# inktimev6.net
KiCad netlist of a schematic drawn in EAGLE
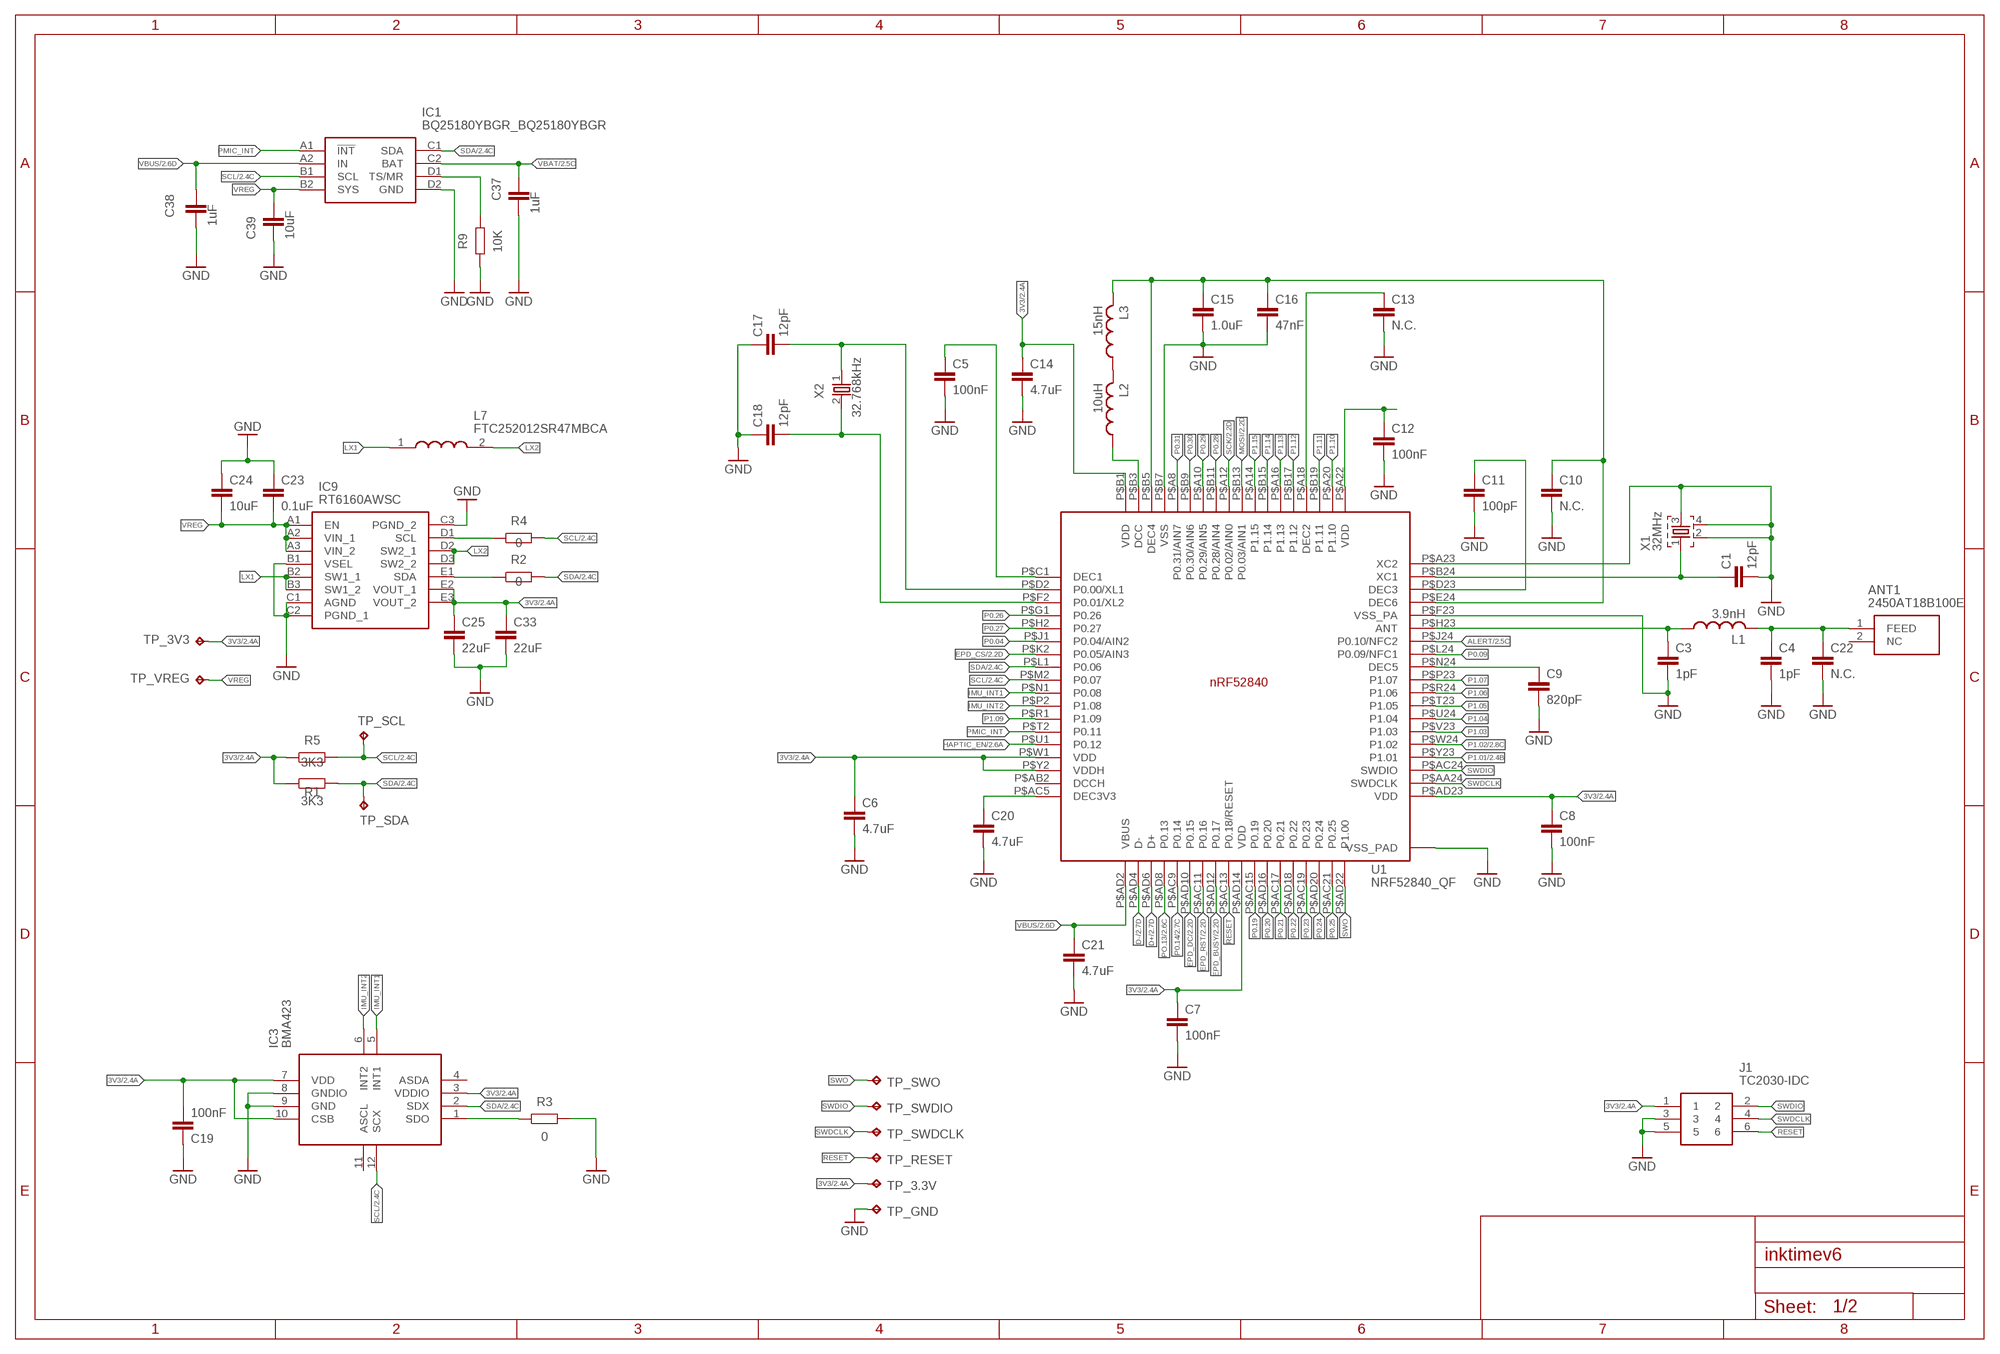
[diagram p0: schematic, sheet 1]
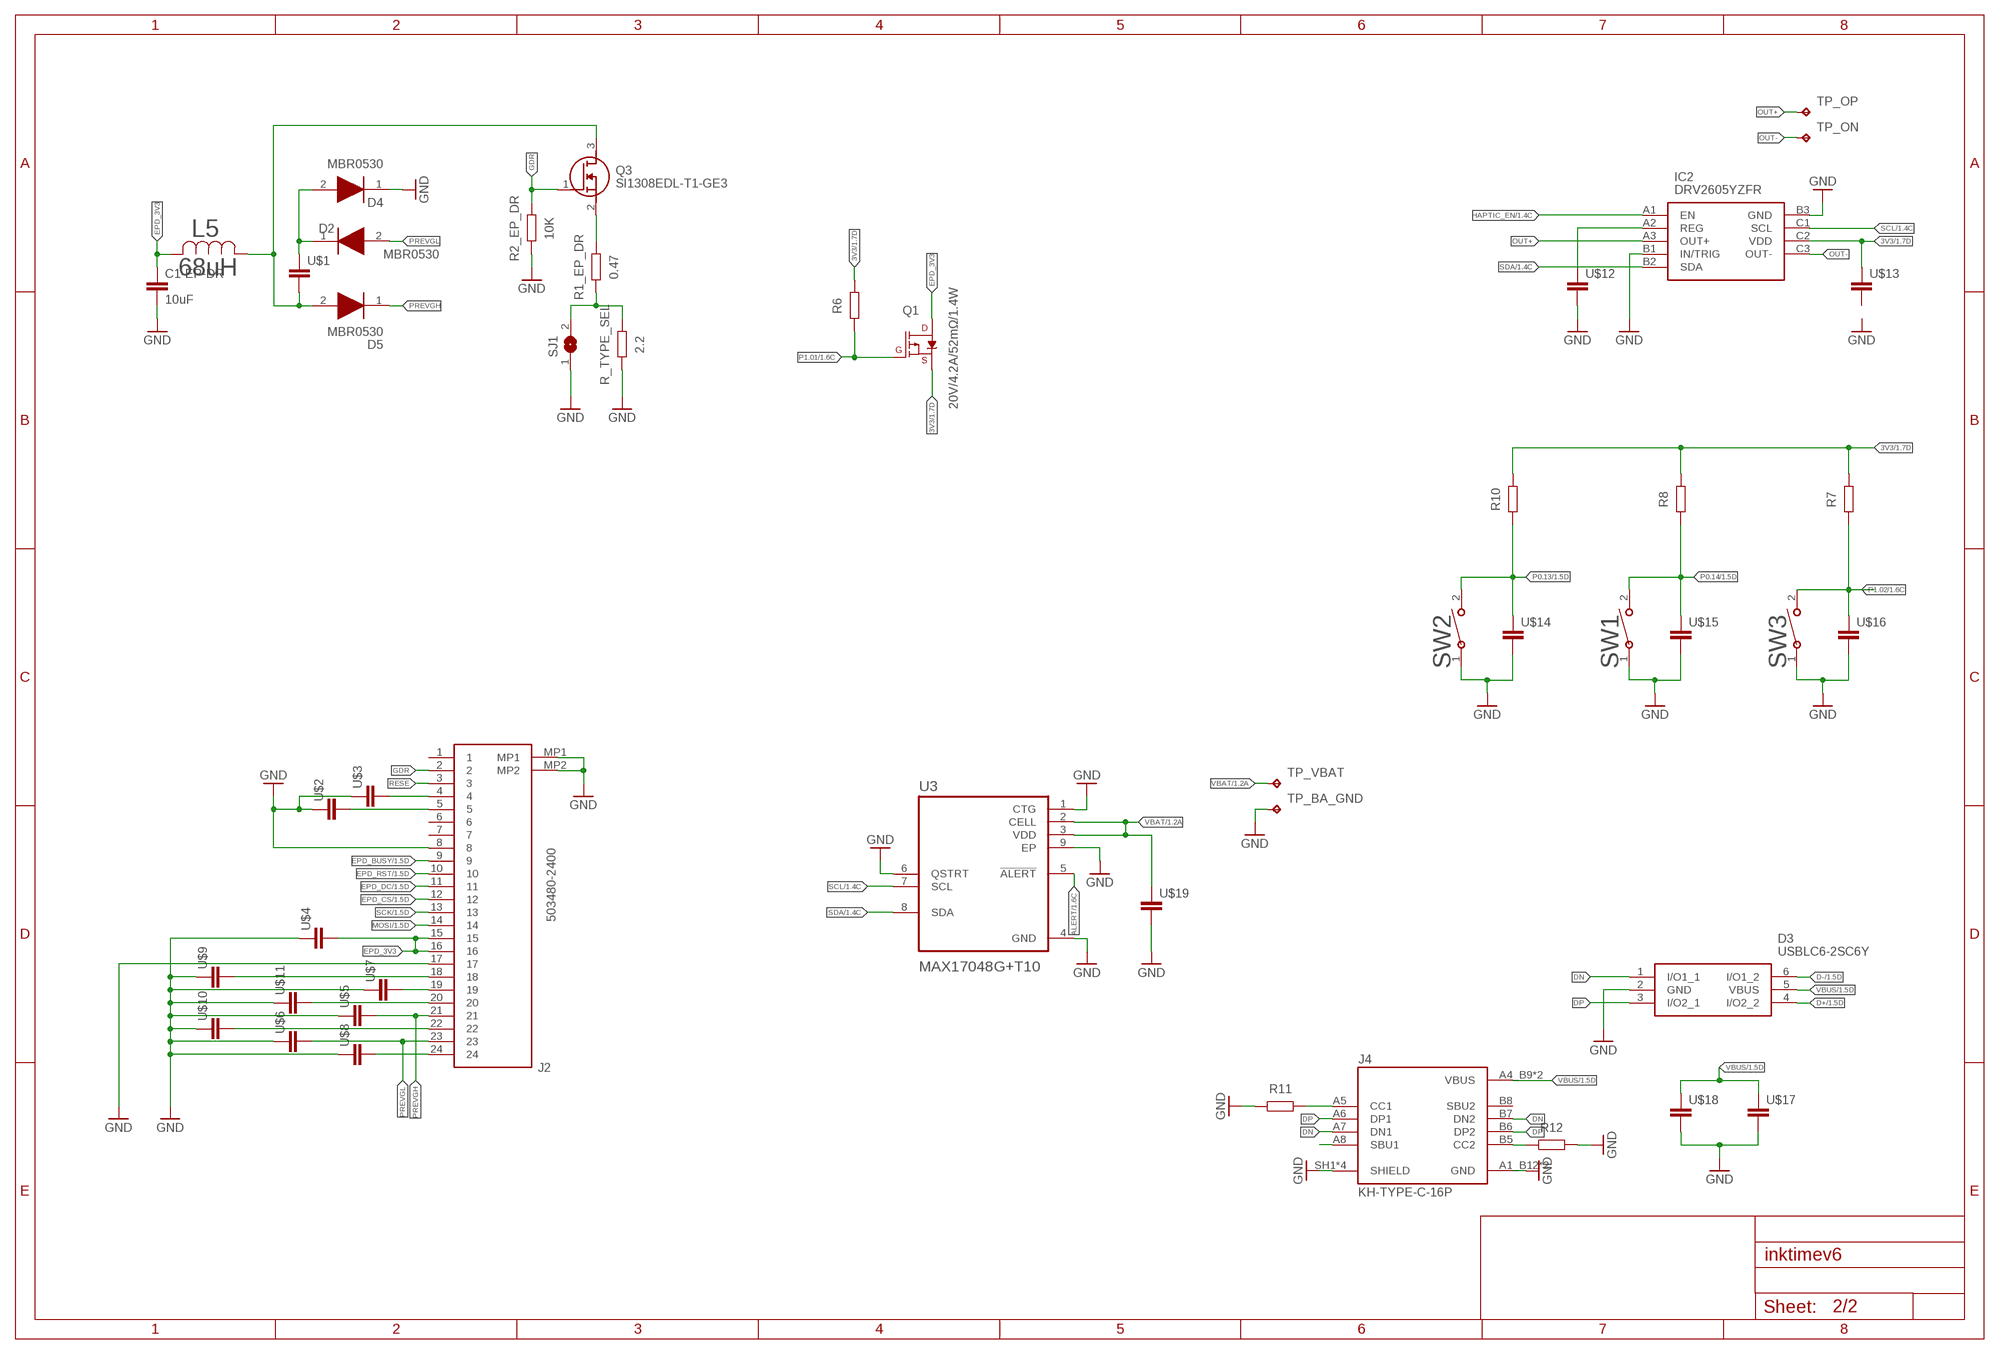
[diagram p1: schematic, sheet 2]

(export (version "E")
  (design (tool "Eeschema 10.0.6"))
  (components
    (comp (ref "C1-EP-DR")
      (value "10uF")
      (footprint "eagle-import:NORDIC_NRF_3_RESC0201_L")
      (libsource (lib "eagle-import") (part "NORDIC_NRF_3_CAPACITOR_0201_L"))
    )
    (comp (ref "D2")
      (value "MBR0530")
      (footprint "eagle-import:ESP32_C6_LIBRARY_5_SOD3716X135N")
      (fields (field (name "MF") "ON Semiconductor"))
      (libsource (lib "eagle-import") (part "ESP32_C6_LIBRARY_5_MBR0530"))
    )
    (comp (ref "D3")
      (value "USBLC6-2SC6Y")
      (footprint "eagle-import:ESP32_C6_LIBRARY_3_SOT95P280X145-6N")
      (fields (field (name "MF") "STMicroelectronics"))
      (libsource (lib "eagle-import") (part "ESP32_C6_LIBRARY_3_USBLC6-2SC6Y"))
    )
    (comp (ref "D4")
      (value "MBR0530")
      (footprint "eagle-import:ESP32_C6_LIBRARY_5_SOD3716X135N")
      (fields (field (name "MF") "ON Semiconductor"))
      (libsource (lib "eagle-import") (part "ESP32_C6_LIBRARY_5_MBR0530"))
    )
    (comp (ref "D5")
      (value "MBR0530")
      (footprint "eagle-import:ESP32_C6_LIBRARY_5_SOD3716X135N")
      (fields (field (name "MF") "ON Semiconductor"))
      (libsource (lib "eagle-import") (part "ESP32_C6_LIBRARY_5_MBR0530"))
    )
    (comp (ref "IC2")
      (value "DRV2605YZFR")
      (footprint "eagle-import:DRV2605YZFR_BGA9C50P3X3_144X144X62")
      (libsource (lib "eagle-import") (part "DRV2605YZFR_DRV2605YZFR"))
    )
    (comp (ref "J2")
      (value "503480-2400")
      (footprint "eagle-import:503480-2400_5034802400")
      (fields (field (name "MOUSER_PART_NUMBER") "538-503480-2400"))
      (libsource (lib "eagle-import") (part "503480-2400_503480-2400"))
    )
    (comp (ref "J4")
      (value "KH-TYPE-C-16P")
      (footprint "eagle-import:KH-TYPE-C-16P_KINGHELM_KH-TYPE-C-16P")
      (fields (field (name "MF") "kinghelm"))
      (libsource (lib "eagle-import") (part "KH-TYPE-C-16P_KH-TYPE-C-16P"))
    )
    (comp (ref "L5")
      (value "68uH")
      (footprint "eagle-import:ESP32_C6_LIBRARY_2_IND_4828-WE-TPC_WRE")
      (fields
        (field (name "MANUFACTURER_PART_NUMBER") "744043680")
        (field (name "COPYRIGHT") "Copyright (C) 2024 Ultra Librarian. All rights reserved.")
      )
      (libsource (lib "eagle-import") (part "ESP32_C6_LIBRARY_2_744043680IND_4828-WE-TPC_WRE"))
    )
    (comp (ref "Q1")
      (value "20V/4.2A/52mΩ/1.4W")
      (footprint "eagle-import:ESP32_C6_LIBRARY_4_ESP32_C6_LIBRARY_4_ESP32_C6_LIBRARY_4_ESP32_C6_LIBRARY_4_ESP32_WROVER_SPARKFUN-DISCRETESEMI_SOT23-3")
      (libsource (lib "eagle-import") (part "ESP32_C6_LIBRARY_4_ESP32_WROVER_SPARKFUN-DISCRETESEMI_MOSFET_PCH-DMG2305UX-7"))
    )
    (comp (ref "Q3")
      (value "SI1308EDL-T1-GE3")
      (footprint "eagle-import:ESP32_C6_LIBRARY_6_SOT65P210X110-3N")
      (fields (field (name "MF") "Vishay Siliconix"))
      (libsource (lib "eagle-import") (part "ESP32_C6_LIBRARY_6_SI1308EDL-T1-GE3"))
    )
    (comp (ref "R1_EP_DR")
      (value "0.47")
      (footprint "eagle-import:RESC1005X40")
      (libsource (lib "eagle-import") (part "RCHIP-0402(1005-METRIC)_"))
    )
    (comp (ref "R2_EP_DR")
      (value "10K")
      (footprint "eagle-import:RESC1005X40")
      (libsource (lib "eagle-import") (part "RCHIP-0402(1005-METRIC)_"))
    )
    (comp (ref "R6")
      (value "R_CHIP-0402(1005-METRIC)")
      (footprint "eagle-import:RESC1005X40")
      (libsource (lib "eagle-import") (part "RCHIP-0402(1005-METRIC)_"))
    )
    (comp (ref "R7")
      (value "R_CHIP-0402(1005-METRIC)")
      (footprint "eagle-import:RESC1005X40")
      (libsource (lib "eagle-import") (part "RCHIP-0402(1005-METRIC)_"))
    )
    (comp (ref "R8")
      (value "R_CHIP-0402(1005-METRIC)")
      (footprint "eagle-import:RESC1005X40")
      (libsource (lib "eagle-import") (part "RCHIP-0402(1005-METRIC)_"))
    )
    (comp (ref "R10")
      (value "R_CHIP-0402(1005-METRIC)")
      (footprint "eagle-import:RESC1005X40")
      (libsource (lib "eagle-import") (part "RCHIP-0402(1005-METRIC)_"))
    )
    (comp (ref "R11")
      (value "R_CHIP-0402(1005-METRIC)")
      (footprint "eagle-import:RESC1005X40")
      (libsource (lib "eagle-import") (part "RCHIP-0402(1005-METRIC)_"))
    )
    (comp (ref "R12")
      (value "R_CHIP-0402(1005-METRIC)")
      (footprint "eagle-import:RESC1005X40")
      (libsource (lib "eagle-import") (part "RCHIP-0402(1005-METRIC)_"))
    )
    (comp (ref "R_TYPE_SEL")
      (value "2.2")
      (footprint "eagle-import:RESC1005X40")
      (libsource (lib "eagle-import") (part "RCHIP-0402(1005-METRIC)_"))
    )
    (comp (ref "SJ1")
      (value "ESP32_C6_LIBRARY_7_JUMPER_SJ")
      (footprint "eagle-import:ESP32_C6_LIBRARY_7_JUMPER_SJ")
      (libsource (lib "eagle-import") (part "ESP32_C6_LIBRARY_7_JUMPER_SJ"))
    )
    (comp (ref "SW1")
      (value "2025-10-22_07-23-44_LIBRARY_EVP-AKE31ASW_EVP-AKE31A_PAN")
      (footprint "eagle-import:2025-10-22_07-23-44_LIBRARY_SW_EVP-AKE31A_PAN")
      (fields
        (field (name "MANUFACTURER_PART_NUMBER") "EVP-AKE31A")
        (field (name "COPYRIGHT") "Copyright (C) 2025 Ultra Librarian. All rights reserved.")
      )
      (libsource (lib "eagle-import") (part "2025-10-22_07-23-44_LIBRARY_EVP-AKE31ASW_EVP-AKE31A_PAN"))
    )
    (comp (ref "SW2")
      (value "2025-10-22_07-23-44_LIBRARY_EVP-AKE31ASW_EVP-AKE31A_PAN")
      (footprint "eagle-import:2025-10-22_07-23-44_LIBRARY_SW_EVP-AKE31A_PAN")
      (fields
        (field (name "MANUFACTURER_PART_NUMBER") "EVP-AKE31A")
        (field (name "COPYRIGHT") "Copyright (C) 2025 Ultra Librarian. All rights reserved.")
      )
      (libsource (lib "eagle-import") (part "2025-10-22_07-23-44_LIBRARY_EVP-AKE31ASW_EVP-AKE31A_PAN"))
    )
    (comp (ref "SW3")
      (value "2025-10-22_07-23-44_LIBRARY_EVP-AKE31ASW_EVP-AKE31A_PAN")
      (footprint "eagle-import:2025-10-22_07-23-44_LIBRARY_SW_EVP-AKE31A_PAN")
      (fields
        (field (name "MANUFACTURER_PART_NUMBER") "EVP-AKE31A")
        (field (name "COPYRIGHT") "Copyright (C) 2025 Ultra Librarian. All rights reserved.")
      )
      (libsource (lib "eagle-import") (part "2025-10-22_07-23-44_LIBRARY_EVP-AKE31ASW_EVP-AKE31A_PAN"))
    )
    (comp (ref "TP_BA_GND")
      (value "HECTOR_WATCH_1_TPTP20R")
      (footprint "eagle-import:HECTOR_WATCH_1_TP20R")
      (libsource (lib "eagle-import") (part "HECTOR_WATCH_1_TPTP20R"))
    )
    (comp (ref "TP_ON")
      (value "HECTOR_WATCH_1_TPTP20R")
      (footprint "eagle-import:HECTOR_WATCH_1_TP20R")
      (libsource (lib "eagle-import") (part "HECTOR_WATCH_1_TPTP20R"))
    )
    (comp (ref "TP_OP")
      (value "HECTOR_WATCH_1_TPTP20R")
      (footprint "eagle-import:HECTOR_WATCH_1_TP20R")
      (libsource (lib "eagle-import") (part "HECTOR_WATCH_1_TPTP20R"))
    )
    (comp (ref "TP_VBAT")
      (value "HECTOR_WATCH_1_TPTP20R")
      (footprint "eagle-import:HECTOR_WATCH_1_TP20R")
      (libsource (lib "eagle-import") (part "HECTOR_WATCH_1_TPTP20R"))
    )
    (comp (ref "U$1")
      (value "NORDIC_NRF_3_CAPACITOR_0201_L")
      (footprint "eagle-import:NORDIC_NRF_3_RESC0201_L")
      (libsource (lib "eagle-import") (part "NORDIC_NRF_3_CAPACITOR_0201_L"))
    )
    (comp (ref "U$2")
      (value "NORDIC_NRF_3_CAPACITOR_0201_L")
      (footprint "eagle-import:NORDIC_NRF_3_RESC0201_L")
      (libsource (lib "eagle-import") (part "NORDIC_NRF_3_CAPACITOR_0201_L"))
    )
    (comp (ref "U$3")
      (value "NORDIC_NRF_3_CAPACITOR_0201_L")
      (footprint "eagle-import:NORDIC_NRF_3_RESC0201_L")
      (libsource (lib "eagle-import") (part "NORDIC_NRF_3_CAPACITOR_0201_L"))
    )
    (comp (ref "U$4")
      (value "NORDIC_NRF_3_CAPACITOR_0201_L")
      (footprint "eagle-import:NORDIC_NRF_3_RESC0201_L")
      (libsource (lib "eagle-import") (part "NORDIC_NRF_3_CAPACITOR_0201_L"))
    )
    (comp (ref "U$5")
      (value "NORDIC_NRF_3_CAPACITOR_0201_L")
      (footprint "eagle-import:NORDIC_NRF_3_RESC0201_L")
      (libsource (lib "eagle-import") (part "NORDIC_NRF_3_CAPACITOR_0201_L"))
    )
    (comp (ref "U$6")
      (value "NORDIC_NRF_3_CAPACITOR_0201_L")
      (footprint "eagle-import:NORDIC_NRF_3_RESC0201_L")
      (libsource (lib "eagle-import") (part "NORDIC_NRF_3_CAPACITOR_0201_L"))
    )
    (comp (ref "U$7")
      (value "NORDIC_NRF_3_CAPACITOR_0201_L")
      (footprint "eagle-import:NORDIC_NRF_3_RESC0201_L")
      (libsource (lib "eagle-import") (part "NORDIC_NRF_3_CAPACITOR_0201_L"))
    )
    (comp (ref "U$8")
      (value "NORDIC_NRF_3_CAPACITOR_0201_L")
      (footprint "eagle-import:NORDIC_NRF_3_RESC0201_L")
      (libsource (lib "eagle-import") (part "NORDIC_NRF_3_CAPACITOR_0201_L"))
    )
    (comp (ref "U$9")
      (value "NORDIC_NRF_3_CAPACITOR_0201_L")
      (footprint "eagle-import:NORDIC_NRF_3_RESC0201_L")
      (libsource (lib "eagle-import") (part "NORDIC_NRF_3_CAPACITOR_0201_L"))
    )
    (comp (ref "U$10")
      (value "NORDIC_NRF_3_CAPACITOR_0201_L")
      (footprint "eagle-import:NORDIC_NRF_3_RESC0201_L")
      (libsource (lib "eagle-import") (part "NORDIC_NRF_3_CAPACITOR_0201_L"))
    )
    (comp (ref "U$11")
      (value "NORDIC_NRF_3_CAPACITOR_0201_L")
      (footprint "eagle-import:NORDIC_NRF_3_RESC0201_L")
      (libsource (lib "eagle-import") (part "NORDIC_NRF_3_CAPACITOR_0201_L"))
    )
    (comp (ref "U$12")
      (value "NORDIC_NRF_3_CAPACITOR_0201_L")
      (footprint "eagle-import:NORDIC_NRF_3_RESC0201_L")
      (libsource (lib "eagle-import") (part "NORDIC_NRF_3_CAPACITOR_0201_L"))
    )
    (comp (ref "U$13")
      (value "NORDIC_NRF_3_CAPACITOR_0201_L")
      (footprint "eagle-import:NORDIC_NRF_3_RESC0201_L")
      (libsource (lib "eagle-import") (part "NORDIC_NRF_3_CAPACITOR_0201_L"))
    )
    (comp (ref "U$14")
      (value "NORDIC_NRF_3_CAPACITOR_0201_L")
      (footprint "eagle-import:NORDIC_NRF_3_RESC0201_L")
      (libsource (lib "eagle-import") (part "NORDIC_NRF_3_CAPACITOR_0201_L"))
    )
    (comp (ref "U$15")
      (value "NORDIC_NRF_3_CAPACITOR_0201_L")
      (footprint "eagle-import:NORDIC_NRF_3_RESC0201_L")
      (libsource (lib "eagle-import") (part "NORDIC_NRF_3_CAPACITOR_0201_L"))
    )
    (comp (ref "U$16")
      (value "NORDIC_NRF_3_CAPACITOR_0201_L")
      (footprint "eagle-import:NORDIC_NRF_3_RESC0201_L")
      (libsource (lib "eagle-import") (part "NORDIC_NRF_3_CAPACITOR_0201_L"))
    )
    (comp (ref "U$17")
      (value "NORDIC_NRF_3_CAPACITOR_0201_L")
      (footprint "eagle-import:NORDIC_NRF_3_RESC0201_L")
      (libsource (lib "eagle-import") (part "NORDIC_NRF_3_CAPACITOR_0201_L"))
    )
    (comp (ref "U$18")
      (value "NORDIC_NRF_3_CAPACITOR_0201_L")
      (footprint "eagle-import:NORDIC_NRF_3_RESC0201_L")
      (libsource (lib "eagle-import") (part "NORDIC_NRF_3_CAPACITOR_0201_L"))
    )
    (comp (ref "U$19")
      (value "NORDIC_NRF_3_CAPACITOR_0201_L")
      (footprint "eagle-import:NORDIC_NRF_3_RESC0201_L")
      (libsource (lib "eagle-import") (part "NORDIC_NRF_3_CAPACITOR_0201_L"))
    )
    (comp (ref "U3")
      (value "MAX17048G+T10")
      (footprint "eagle-import:ESP32_C6_LIBRARY_SON50P200X200X80-9N")
      (fields (field (name "MF") "Analog Devices"))
      (libsource (lib "eagle-import") (part "ESP32_C6_LIBRARY_MAX17048G+T10"))
    )
    (comp (ref "ANT1")
      (value "2450AT18B100E")
      (footprint "eagle-import:2450AT18B100E_ANTC3216X140N")
      (fields (field (name "MOUSER_PART_NUMBER") "609-2450AT18B100E"))
      (libsource (lib "eagle-import") (part "2450AT18B100E_2450AT18B100E"))
    )
    (comp (ref "C1")
      (value "12pF")
      (footprint "eagle-import:NORDIC_NRF_3_RESC0201_L")
      (libsource (lib "eagle-import") (part "NORDIC_NRF_3_CAPACITOR_0201_L"))
    )
    (comp (ref "C3")
      (value "1pF")
      (footprint "eagle-import:NORDIC_NRF_3_RESC0201_L")
      (libsource (lib "eagle-import") (part "NORDIC_NRF_3_CAPACITOR_0201_L"))
    )
    (comp (ref "C4")
      (value "1pF")
      (footprint "eagle-import:NORDIC_NRF_3_RESC0201_L")
      (libsource (lib "eagle-import") (part "NORDIC_NRF_3_CAPACITOR_0201_L"))
    )
    (comp (ref "C5")
      (value "100nF")
      (footprint "eagle-import:NORDIC_NRF_3_RESC0201_L")
      (libsource (lib "eagle-import") (part "NORDIC_NRF_3_CAPACITOR_0201_L"))
    )
    (comp (ref "C6")
      (value "4.7uF")
      (footprint "eagle-import:NORDIC_NRF_3_RESC0201_L")
      (libsource (lib "eagle-import") (part "NORDIC_NRF_3_CAPACITOR_0201_L"))
    )
    (comp (ref "C7")
      (value "100nF")
      (footprint "eagle-import:NORDIC_NRF_3_RESC0201_L")
      (libsource (lib "eagle-import") (part "NORDIC_NRF_3_CAPACITOR_0201_L"))
    )
    (comp (ref "C8")
      (value "100nF")
      (footprint "eagle-import:NORDIC_NRF_3_RESC0201_L")
      (libsource (lib "eagle-import") (part "NORDIC_NRF_3_CAPACITOR_0201_L"))
    )
    (comp (ref "C9")
      (value "820pF")
      (footprint "eagle-import:NORDIC_NRF_3_RESC0201_L")
      (libsource (lib "eagle-import") (part "NORDIC_NRF_3_CAPACITOR_0201_L"))
    )
    (comp (ref "C10")
      (value "N.C.")
      (footprint "eagle-import:NORDIC_NRF_3_RESC0201_L")
      (libsource (lib "eagle-import") (part "NORDIC_NRF_3_CAPACITOR_0201_L"))
    )
    (comp (ref "C11")
      (value "100pF")
      (footprint "eagle-import:NORDIC_NRF_3_RESC0201_L")
      (libsource (lib "eagle-import") (part "NORDIC_NRF_3_CAPACITOR_0201_L"))
    )
    (comp (ref "C12")
      (value "100nF")
      (footprint "eagle-import:NORDIC_NRF_3_RESC0201_L")
      (libsource (lib "eagle-import") (part "NORDIC_NRF_3_CAPACITOR_0201_L"))
    )
    (comp (ref "C13")
      (value "N.C.")
      (footprint "eagle-import:NORDIC_NRF_3_RESC0201_L")
      (libsource (lib "eagle-import") (part "NORDIC_NRF_3_CAPACITOR_0201_L"))
    )
    (comp (ref "C14")
      (value "4.7uF")
      (footprint "eagle-import:NORDIC_NRF_3_RESC0201_L")
      (libsource (lib "eagle-import") (part "NORDIC_NRF_3_CAPACITOR_0201_L"))
    )
    (comp (ref "C15")
      (value "1.0uF")
      (footprint "eagle-import:NORDIC_NRF_3_RESC0201_L")
      (libsource (lib "eagle-import") (part "NORDIC_NRF_3_CAPACITOR_0201_L"))
    )
    (comp (ref "C16")
      (value "47nF")
      (footprint "eagle-import:NORDIC_NRF_3_RESC0201_L")
      (libsource (lib "eagle-import") (part "NORDIC_NRF_3_CAPACITOR_0201_L"))
    )
    (comp (ref "C17")
      (value "12pF")
      (footprint "eagle-import:NORDIC_NRF_3_RESC0201_L")
      (libsource (lib "eagle-import") (part "NORDIC_NRF_3_CAPACITOR_0201_L"))
    )
    (comp (ref "C18")
      (value "12pF")
      (footprint "eagle-import:NORDIC_NRF_3_RESC0201_L")
      (libsource (lib "eagle-import") (part "NORDIC_NRF_3_CAPACITOR_0201_L"))
    )
    (comp (ref "C19")
      (value "100nF")
      (footprint "eagle-import:NORDIC_NRF_3_RESC0201_L")
      (libsource (lib "eagle-import") (part "NORDIC_NRF_3_CAPACITOR_0201_L"))
    )
    (comp (ref "C20")
      (value "4.7uF")
      (footprint "eagle-import:NORDIC_NRF_3_RESC0201_L")
      (libsource (lib "eagle-import") (part "NORDIC_NRF_3_CAPACITOR_0201_L"))
    )
    (comp (ref "C21")
      (value "4.7uF")
      (footprint "eagle-import:NORDIC_NRF_3_RESC0201_L")
      (libsource (lib "eagle-import") (part "NORDIC_NRF_3_CAPACITOR_0201_L"))
    )
    (comp (ref "C22")
      (value "N.C.")
      (footprint "eagle-import:NORDIC_NRF_3_RESC0201_L")
      (libsource (lib "eagle-import") (part "NORDIC_NRF_3_CAPACITOR_0201_L"))
    )
    (comp (ref "C23")
      (value "0.1uF")
      (footprint "eagle-import:NORDIC_NRF_3_RESC0201_L")
      (libsource (lib "eagle-import") (part "NORDIC_NRF_3_CAPACITOR_0201_L"))
    )
    (comp (ref "C24")
      (value "10uF")
      (footprint "eagle-import:NORDIC_NRF_3_RESC0201_L")
      (libsource (lib "eagle-import") (part "NORDIC_NRF_3_CAPACITOR_0201_L"))
    )
    (comp (ref "C25")
      (value "22uF")
      (footprint "eagle-import:NORDIC_NRF_3_RESC0201_L")
      (libsource (lib "eagle-import") (part "NORDIC_NRF_3_CAPACITOR_0201_L"))
    )
    (comp (ref "C33")
      (value "22uF")
      (footprint "eagle-import:NORDIC_NRF_3_RESC0201_L")
      (libsource (lib "eagle-import") (part "NORDIC_NRF_3_CAPACITOR_0201_L"))
    )
    (comp (ref "C37")
      (value "1uF")
      (footprint "eagle-import:PERFECT_0402_0402")
      (libsource (lib "eagle-import") (part "PERFECT_0402_CAP_0402"))
    )
    (comp (ref "C38")
      (value "1uF")
      (footprint "eagle-import:NORDIC_NRF_3_RESC0201_L")
      (libsource (lib "eagle-import") (part "NORDIC_NRF_3_CAPACITOR_0201_L"))
    )
    (comp (ref "C39")
      (value "10uF")
      (footprint "eagle-import:PERFECT_0402_0402")
      (libsource (lib "eagle-import") (part "PERFECT_0402_CAP_0402"))
    )
    (comp (ref "IC1")
      (value "BQ25180YBGR_BQ25180YBGR")
      (footprint "eagle-import:BQ25180YBGR_BGA8C40P2X4_100X155X50")
      (fields
        (field (name "ARROW_PART_NUMBER") "BQ25180YBGR")
        (field (name "MOUSER_PART_NUMBER") "595-BQ25180YBGR")
      )
      (libsource (lib "eagle-import") (part "BQ25180YBGR_BQ25180YBGR"))
    )
    (comp (ref "IC3")
      (value "BMA423")
      (footprint "eagle-import:BMA423_BMA423")
      (fields (field (name "MOUSER_PART_NUMBER") "262-BMA423"))
      (libsource (lib "eagle-import") (part "BMA423_BMA423"))
    )
    (comp (ref "IC9")
      (value "RT6160AWSC")
      (footprint "eagle-import:RT6160AWSC_BGA15C40P3X5_140X230X60")
      (fields (field (name "MOUSER_PART_NUMBER") "835-RT6160AWSC"))
      (libsource (lib "eagle-import") (part "RT6160AWSC_RT6160AWSC"))
    )
    (comp (ref "J1")
      (value "TC2030-IDC")
      (footprint "eagle-import:TC2030-IDC_TC2030IDC")
      (libsource (lib "eagle-import") (part "TC2030-IDC_TC2030-IDC"))
    )
    (comp (ref "L1")
      (value "3.9nH")
      (footprint "eagle-import:NORDIC_NRF_2_RESC0402_L")
      (libsource (lib "eagle-import") (part "NORDIC_NRF_2_INDUCTOR_0402_L"))
    )
    (comp (ref "L2")
      (value "10uH")
      (footprint "eagle-import:NORDIC_NRF_2_RESC0402_L")
      (libsource (lib "eagle-import") (part "NORDIC_NRF_2_INDUCTOR_0402_L"))
    )
    (comp (ref "L3")
      (value "15nH")
      (footprint "eagle-import:NORDIC_NRF_2_RESC0402_L")
      (libsource (lib "eagle-import") (part "NORDIC_NRF_2_INDUCTOR_0402_L"))
    )
    (comp (ref "L7")
      (value "FTC252012SR47MBCA")
      (footprint "eagle-import:MLP2016SR47MT0S1_INDC2016X100N")
      (libsource (lib "eagle-import") (part "MLP2016SR47MT0S1_FTC252012SR47MBCA"))
    )
    (comp (ref "R1")
      (value "3K3")
      (footprint "eagle-import:RESC1005X40")
      (libsource (lib "eagle-import") (part "RCHIP-0402(1005-METRIC)_"))
    )
    (comp (ref "R2")
      (value "0")
      (footprint "eagle-import:RESC1005X40")
      (libsource (lib "eagle-import") (part "RCHIP-0402(1005-METRIC)_"))
    )
    (comp (ref "R3")
      (value "0")
      (footprint "eagle-import:RESC1005X40")
      (libsource (lib "eagle-import") (part "RCHIP-0402(1005-METRIC)_"))
    )
    (comp (ref "R4")
      (value "0")
      (footprint "eagle-import:RESC1005X40")
      (libsource (lib "eagle-import") (part "RCHIP-0402(1005-METRIC)_"))
    )
    (comp (ref "R5")
      (value "3K3")
      (footprint "eagle-import:RESC1005X40")
      (libsource (lib "eagle-import") (part "RCHIP-0402(1005-METRIC)_"))
    )
    (comp (ref "R9")
      (value "10K")
      (footprint "eagle-import:RESC1005X40")
      (libsource (lib "eagle-import") (part "RCHIP-0402(1005-METRIC)_"))
    )
    (comp (ref "TP_3.3V")
      (value "HECTOR_WATCH_1_TPTP20R")
      (footprint "eagle-import:HECTOR_WATCH_1_TP20R")
      (libsource (lib "eagle-import") (part "HECTOR_WATCH_1_TPTP20R"))
    )
    (comp (ref "TP_3V3")
      (value "HECTOR_WATCH_1_TPTP20R")
      (footprint "eagle-import:HECTOR_WATCH_1_TP20R")
      (libsource (lib "eagle-import") (part "HECTOR_WATCH_1_TPTP20R"))
    )
    (comp (ref "TP_GND")
      (value "HECTOR_WATCH_1_TPTP20R")
      (footprint "eagle-import:HECTOR_WATCH_1_TP20R")
      (libsource (lib "eagle-import") (part "HECTOR_WATCH_1_TPTP20R"))
    )
    (comp (ref "TP_RESET")
      (value "HECTOR_WATCH_1_TPTP20R")
      (footprint "eagle-import:HECTOR_WATCH_1_TP20R")
      (libsource (lib "eagle-import") (part "HECTOR_WATCH_1_TPTP20R"))
    )
    (comp (ref "TP_SCL")
      (value "HECTOR_WATCH_1_TPTP20R")
      (footprint "eagle-import:HECTOR_WATCH_1_TP20R")
      (libsource (lib "eagle-import") (part "HECTOR_WATCH_1_TPTP20R"))
    )
    (comp (ref "TP_SDA")
      (value "HECTOR_WATCH_1_TPTP20R")
      (footprint "eagle-import:HECTOR_WATCH_1_TP20R")
      (libsource (lib "eagle-import") (part "HECTOR_WATCH_1_TPTP20R"))
    )
    (comp (ref "TP_SWDCLK")
      (value "HECTOR_WATCH_1_TPTP20R")
      (footprint "eagle-import:HECTOR_WATCH_1_TP20R")
      (libsource (lib "eagle-import") (part "HECTOR_WATCH_1_TPTP20R"))
    )
    (comp (ref "TP_SWDIO")
      (value "HECTOR_WATCH_1_TPTP20R")
      (footprint "eagle-import:HECTOR_WATCH_1_TP20R")
      (libsource (lib "eagle-import") (part "HECTOR_WATCH_1_TPTP20R"))
    )
    (comp (ref "TP_SWO")
      (value "HECTOR_WATCH_1_TPTP20R")
      (footprint "eagle-import:HECTOR_WATCH_1_TP20R")
      (libsource (lib "eagle-import") (part "HECTOR_WATCH_1_TPTP20R"))
    )
    (comp (ref "TP_VREG")
      (value "HECTOR_WATCH_1_TPTP20R")
      (footprint "eagle-import:HECTOR_WATCH_1_TP20R")
      (libsource (lib "eagle-import") (part "HECTOR_WATCH_1_TPTP20R"))
    )
    (comp (ref "U1")
      (value "NRF52840_QF")
      (footprint "eagle-import:NORDIC_NRF_4_AQFN50P700X700X85_HS-74N")
      (libsource (lib "eagle-import") (part "NORDIC_NRF_4_NRF52840_QF"))
    )
    (comp (ref "X1")
      (value "32MHz")
      (footprint "eagle-import:NORDIC_NRF_BT-XTAL_2016_N")
      (libsource (lib "eagle-import") (part "NORDIC_NRF_XTAL_32MHZ"))
    )
    (comp (ref "X2")
      (value "32.768kHz")
      (footprint "eagle-import:NORDIC_NRF_1_XTAL_3215_N")
      (libsource (lib "eagle-import") (part "NORDIC_NRF_1_XTAL_32KHZ"))
    )
  )
  (nets
    (net (code "1") (name "3V3{slash}1.7D") (class "Default")
      (node (ref "IC2") (pin "C2") (pinfunction "VDD_C2") (pintype "bidirectional"))
      (node (ref "Q1") (pin "2") (pinfunction "S_2") (pintype "bidirectional"))
      (node (ref "R10") (pin "2") (pinfunction "2_2") (pintype "passive"))
      (node (ref "R6") (pin "2") (pinfunction "2_2") (pintype "passive"))
      (node (ref "R7") (pin "2") (pinfunction "2_2") (pintype "passive"))
      (node (ref "R8") (pin "2") (pinfunction "2_2") (pintype "passive"))
      (node (ref "U$13") (pin "1") (pinfunction "1_1") (pintype "passive"))
    )
    (net (code "2") (name "3V3{slash}2.4A") (class "Default")
      (node (ref "C14") (pin "2") (pinfunction "2_2") (pintype "passive"))
      (node (ref "C19") (pin "2") (pinfunction "2_2") (pintype "passive"))
      (node (ref "C25") (pin "2") (pinfunction "2_2") (pintype "passive"))
      (node (ref "C33") (pin "2") (pinfunction "2_2") (pintype "passive"))
      (node (ref "C6") (pin "2") (pinfunction "2_2") (pintype "passive"))
      (node (ref "C7") (pin "2") (pinfunction "2_2") (pintype "passive"))
      (node (ref "C8") (pin "2") (pinfunction "2_2") (pintype "passive"))
      (node (ref "IC3") (pin "10") (pinfunction "CSB_10") (pintype "bidirectional"))
      (node (ref "IC3") (pin "3") (pinfunction "VDDIO_3") (pintype "bidirectional"))
      (node (ref "IC3") (pin "7") (pinfunction "VDD_7") (pintype "bidirectional"))
      (node (ref "IC9") (pin "E2") (pinfunction "VOUT_1_E2") (pintype "bidirectional"))
      (node (ref "IC9") (pin "E3") (pinfunction "VOUT_2_E3") (pintype "bidirectional"))
      (node (ref "J1") (pin "1") (pinfunction "1_1") (pintype "bidirectional"))
      (node (ref "R1") (pin "1") (pinfunction "1_1") (pintype "passive"))
      (node (ref "R5") (pin "1") (pinfunction "1_1") (pintype "passive"))
      (node (ref "TP_3.3V") (pin "TP") (pinfunction "TP_TP") (pintype "input"))
      (node (ref "TP_3V3") (pin "TP") (pinfunction "TP_TP") (pintype "input"))
      (node (ref "U1") (pin "P$AD14") (pinfunction "VDD_P$AD14") (pintype "power_in"))
      (node (ref "U1") (pin "P$AD23") (pinfunction "VDD_P$AD23") (pintype "power_in"))
      (node (ref "U1") (pin "P$B1") (pinfunction "VDD_P$B1") (pintype "power_in"))
      (node (ref "U1") (pin "P$W1") (pinfunction "VDD_P$W1") (pintype "power_in"))
      (node (ref "U1") (pin "P$Y2") (pinfunction "VDDH_P$Y2") (pintype "power_in"))
    )
    (net (code "3") (name "ALERT{slash}1.6C") (class "Default")
      (node (ref "U3") (pin "5") (pinfunction "~{ALERT}_5") (pintype "output"))
    )
    (net (code "4") (name "ALERT{slash}2.5C") (class "Default")
      (node (ref "U1") (pin "P$J24") (pinfunction "P0.10/NFC2_P$J24") (pintype "bidirectional"))
    )
    (net (code "5") (name "D+{slash}1.5D") (class "Default")
      (node (ref "D3") (pin "4") (pinfunction "I/O2_2_4") (pintype "bidirectional"))
    )
    (net (code "6") (name "D+{slash}2.7D") (class "Default")
      (node (ref "U1") (pin "P$AD6") (pinfunction "D+_P$AD6") (pintype "bidirectional"))
    )
    (net (code "7") (name "D-{slash}1.5D") (class "Default")
      (node (ref "D3") (pin "6") (pinfunction "I/O1_2_6") (pintype "bidirectional"))
    )
    (net (code "8") (name "D-{slash}2.7D") (class "Default")
      (node (ref "U1") (pin "P$AD4") (pinfunction "D-_P$AD4") (pintype "bidirectional"))
    )
    (net (code "9") (name "DN") (class "Default")
      (node (ref "D3") (pin "1") (pinfunction "I/O1_1_1") (pintype "bidirectional"))
      (node (ref "J4") (pin "A7") (pinfunction "DN1_A7") (pintype "bidirectional"))
      (node (ref "J4") (pin "B7") (pinfunction "DN2_B7") (pintype "bidirectional"))
    )
    (net (code "10") (name "DP") (class "Default")
      (node (ref "D3") (pin "3") (pinfunction "I/O2_1_3") (pintype "bidirectional"))
      (node (ref "J4") (pin "A6") (pinfunction "DP1_A6") (pintype "bidirectional"))
      (node (ref "J4") (pin "B6") (pinfunction "DP2_B6") (pintype "bidirectional"))
    )
    (net (code "11") (name "EPD_3V3") (class "Default")
      (node (ref "C1-EP-DR") (pin "1") (pinfunction "1_1") (pintype "passive"))
      (node (ref "J2") (pin "15") (pinfunction "15_15") (pintype "bidirectional"))
      (node (ref "J2") (pin "16") (pinfunction "16_16") (pintype "bidirectional"))
      (node (ref "L5") (pin "2") (pinfunction "2_2") (pintype "passive"))
      (node (ref "Q1") (pin "3") (pinfunction "D_3") (pintype "bidirectional"))
      (node (ref "U$4") (pin "2") (pinfunction "2_2") (pintype "passive"))
    )
    (net (code "12") (name "EPD_BUSY{slash}1.5D") (class "Default")
      (node (ref "J2") (pin "9") (pinfunction "9_9") (pintype "bidirectional"))
    )
    (net (code "13") (name "EPD_BUSY{slash}2.2D") (class "Default")
      (node (ref "U1") (pin "P$AD12") (pinfunction "P0.17_P$AD12") (pintype "bidirectional"))
    )
    (net (code "14") (name "EPD_CS{slash}1.5D") (class "Default")
      (node (ref "J2") (pin "12") (pinfunction "12_12") (pintype "bidirectional"))
    )
    (net (code "15") (name "EPD_CS{slash}2.2D") (class "Default")
      (node (ref "U1") (pin "P$K2") (pinfunction "P0.05/AIN3_P$K2") (pintype "bidirectional"))
    )
    (net (code "16") (name "EPD_DC{slash}1.5D") (class "Default")
      (node (ref "J2") (pin "11") (pinfunction "11_11") (pintype "bidirectional"))
    )
    (net (code "17") (name "EPD_DC{slash}2.2D") (class "Default")
      (node (ref "U1") (pin "P$AD10") (pinfunction "P0.15_P$AD10") (pintype "bidirectional"))
    )
    (net (code "18") (name "EPD_RST{slash}1.5D") (class "Default")
      (node (ref "J2") (pin "10") (pinfunction "10_10") (pintype "bidirectional"))
    )
    (net (code "19") (name "EPD_RST{slash}2.2D") (class "Default")
      (node (ref "U1") (pin "P$AC11") (pinfunction "P0.16_P$AC11") (pintype "bidirectional"))
    )
    (net (code "20") (name "GDR") (class "Default")
      (node (ref "J2") (pin "2") (pinfunction "2_2") (pintype "bidirectional"))
      (node (ref "Q3") (pin "1") (pinfunction "G_1") (pintype "bidirectional"))
      (node (ref "R2_EP_DR") (pin "2") (pinfunction "2_2") (pintype "passive"))
    )
    (net (code "21") (name "GND") (class "Default")
      (node (ref "C1") (pin "1") (pinfunction "1_1") (pintype "passive"))
      (node (ref "C1-EP-DR") (pin "2") (pinfunction "2_2") (pintype "passive"))
      (node (ref "C10") (pin "1") (pinfunction "1_1") (pintype "passive"))
      (node (ref "C11") (pin "1") (pinfunction "1_1") (pintype "passive"))
      (node (ref "C12") (pin "1") (pinfunction "1_1") (pintype "passive"))
      (node (ref "C13") (pin "1") (pinfunction "1_1") (pintype "passive"))
      (node (ref "C14") (pin "1") (pinfunction "1_1") (pintype "passive"))
      (node (ref "C15") (pin "1") (pinfunction "1_1") (pintype "passive"))
      (node (ref "C16") (pin "1") (pinfunction "1_1") (pintype "passive"))
      (node (ref "C17") (pin "1") (pinfunction "1_1") (pintype "passive"))
      (node (ref "C18") (pin "1") (pinfunction "1_1") (pintype "passive"))
      (node (ref "C19") (pin "1") (pinfunction "1_1") (pintype "passive"))
      (node (ref "C20") (pin "1") (pinfunction "1_1") (pintype "passive"))
      (node (ref "C21") (pin "1") (pinfunction "1_1") (pintype "passive"))
      (node (ref "C22") (pin "1") (pinfunction "1_1") (pintype "passive"))
      (node (ref "C23") (pin "1") (pinfunction "1_1") (pintype "passive"))
      (node (ref "C24") (pin "1") (pinfunction "1_1") (pintype "passive"))
      (node (ref "C25") (pin "1") (pinfunction "1_1") (pintype "passive"))
      (node (ref "C3") (pin "1") (pinfunction "1_1") (pintype "passive"))
      (node (ref "C33") (pin "1") (pinfunction "1_1") (pintype "passive"))
      (node (ref "C37") (pin "2") (pinfunction "2_2") (pintype "passive"))
      (node (ref "C38") (pin "1") (pinfunction "1_1") (pintype "passive"))
      (node (ref "C39") (pin "2") (pinfunction "2_2") (pintype "passive"))
      (node (ref "C4") (pin "1") (pinfunction "1_1") (pintype "passive"))
      (node (ref "C5") (pin "1") (pinfunction "1_1") (pintype "passive"))
      (node (ref "C6") (pin "1") (pinfunction "1_1") (pintype "passive"))
      (node (ref "C7") (pin "1") (pinfunction "1_1") (pintype "passive"))
      (node (ref "C8") (pin "1") (pinfunction "1_1") (pintype "passive"))
      (node (ref "C9") (pin "1") (pinfunction "1_1") (pintype "passive"))
      (node (ref "D3") (pin "2") (pinfunction "GND_2") (pintype "bidirectional"))
      (node (ref "D4") (pin "1") (pinfunction "K_1") (pintype "bidirectional"))
      (node (ref "IC1") (pin "D2") (pinfunction "GND_D2") (pintype "bidirectional"))
      (node (ref "IC2") (pin "B1") (pinfunction "IN/TRIG_B1") (pintype "bidirectional"))
      (node (ref "IC2") (pin "B3") (pinfunction "GND_B3") (pintype "bidirectional"))
      (node (ref "IC3") (pin "8") (pinfunction "GNDIO_8") (pintype "bidirectional"))
      (node (ref "IC3") (pin "9") (pinfunction "GND_9") (pintype "bidirectional"))
      (node (ref "IC9") (pin "B1") (pinfunction "VSEL_B1") (pintype "bidirectional"))
      (node (ref "IC9") (pin "C1") (pinfunction "AGND_C1") (pintype "bidirectional"))
      (node (ref "IC9") (pin "C2") (pinfunction "PGND_1_C2") (pintype "bidirectional"))
      (node (ref "IC9") (pin "C3") (pinfunction "PGND_2_C3") (pintype "bidirectional"))
      (node (ref "J1") (pin "3") (pinfunction "3_3") (pintype "bidirectional"))
      (node (ref "J1") (pin "5") (pinfunction "5_5") (pintype "bidirectional"))
      (node (ref "J2") (pin "17") (pinfunction "17_17") (pintype "bidirectional"))
      (node (ref "J2") (pin "8") (pinfunction "8_8") (pintype "bidirectional"))
      (node (ref "J2") (pin "MP1") (pinfunction "MP1_MP1") (pintype "bidirectional"))
      (node (ref "J2") (pin "MP2") (pinfunction "MP2_MP2") (pintype "bidirectional"))
      (node (ref "J4") (pin "A12_B1") (pinfunction "GND_A12_B1") (pintype "power_in"))
      (node (ref "J4") (pin "A1_B12") (pinfunction "GND_A1_B12") (pintype "power_in"))
      (node (ref "J4") (pin "SH1") (pinfunction "SHIELD_SH1") (pintype "passive"))
      (node (ref "J4") (pin "SH2") (pinfunction "SHIELD_SH2") (pintype "passive"))
      (node (ref "J4") (pin "SH3") (pinfunction "SHIELD_SH3") (pintype "passive"))
      (node (ref "J4") (pin "SH4") (pinfunction "SHIELD_SH4") (pintype "passive"))
      (node (ref "R11") (pin "1") (pinfunction "1_1") (pintype "passive"))
      (node (ref "R12") (pin "2") (pinfunction "2_2") (pintype "passive"))
      (node (ref "R2_EP_DR") (pin "1") (pinfunction "1_1") (pintype "passive"))
      (node (ref "R3") (pin "2") (pinfunction "2_2") (pintype "passive"))
      (node (ref "R9") (pin "1") (pinfunction "1_1") (pintype "passive"))
      (node (ref "R_TYPE_SEL") (pin "1") (pinfunction "1_1") (pintype "passive"))
      (node (ref "SJ1") (pin "1") (pinfunction "1_1") (pintype "passive"))
      (node (ref "SW1") (pin "1") (pinfunction "1_1") (pintype "passive"))
      (node (ref "SW2") (pin "1") (pinfunction "1_1") (pintype "passive"))
      (node (ref "SW3") (pin "1") (pinfunction "1_1") (pintype "passive"))
      (node (ref "TP_BA_GND") (pin "TP") (pinfunction "TP_TP") (pintype "input"))
      (node (ref "TP_GND") (pin "TP") (pinfunction "TP_TP") (pintype "input"))
      (node (ref "U$10") (pin "1") (pinfunction "1_1") (pintype "passive"))
      (node (ref "U$11") (pin "1") (pinfunction "1_1") (pintype "passive"))
      (node (ref "U$12") (pin "2") (pinfunction "2_2") (pintype "passive"))
      (node (ref "U$14") (pin "2") (pinfunction "2_2") (pintype "passive"))
      (node (ref "U$15") (pin "2") (pinfunction "2_2") (pintype "passive"))
      (node (ref "U$16") (pin "2") (pinfunction "2_2") (pintype "passive"))
      (node (ref "U$17") (pin "2") (pinfunction "2_2") (pintype "passive"))
      (node (ref "U$18") (pin "2") (pinfunction "2_2") (pintype "passive"))
      (node (ref "U$19") (pin "2") (pinfunction "2_2") (pintype "passive"))
      (node (ref "U$2") (pin "1") (pinfunction "1_1") (pintype "passive"))
      (node (ref "U$3") (pin "1") (pinfunction "1_1") (pintype "passive"))
      (node (ref "U$4") (pin "1") (pinfunction "1_1") (pintype "passive"))
      (node (ref "U$5") (pin "1") (pinfunction "1_1") (pintype "passive"))
      (node (ref "U$6") (pin "1") (pinfunction "1_1") (pintype "passive"))
      (node (ref "U$7") (pin "1") (pinfunction "1_1") (pintype "passive"))
      (node (ref "U$8") (pin "1") (pinfunction "1_1") (pintype "passive"))
      (node (ref "U$9") (pin "1") (pinfunction "1_1") (pintype "passive"))
      (node (ref "U1") (pin "P$74") (pinfunction "VSS_PAD_P$74") (pintype "bidirectional"))
      (node (ref "U1") (pin "P$75") (pinfunction "VSS_PAD_P$75") (pintype "bidirectional"))
      (node (ref "U1") (pin "P$76") (pinfunction "VSS_PAD_P$76") (pintype "bidirectional"))
      (node (ref "U1") (pin "P$77") (pinfunction "VSS_PAD_P$77") (pintype "bidirectional"))
      (node (ref "U1") (pin "P$78") (pinfunction "VSS_PAD_P$78") (pintype "bidirectional"))
      (node (ref "U1") (pin "P$79") (pinfunction "VSS_PAD_P$79") (pintype "bidirectional"))
      (node (ref "U1") (pin "P$80") (pinfunction "VSS_PAD_P$80") (pintype "bidirectional"))
      (node (ref "U1") (pin "P$81") (pinfunction "VSS_PAD_P$81") (pintype "bidirectional"))
      (node (ref "U1") (pin "P$82") (pinfunction "VSS_PAD_P$82") (pintype "bidirectional"))
      (node (ref "U1") (pin "P$83") (pinfunction "VSS_PAD_P$83") (pintype "bidirectional"))
      (node (ref "U1") (pin "P$84") (pinfunction "VSS_PAD_P$84") (pintype "bidirectional"))
      (node (ref "U1") (pin "P$85") (pinfunction "VSS_PAD_P$85") (pintype "bidirectional"))
      (node (ref "U1") (pin "P$86") (pinfunction "VSS_PAD_P$86") (pintype "bidirectional"))
      (node (ref "U1") (pin "P$87") (pinfunction "VSS_PAD_P$87") (pintype "bidirectional"))
      (node (ref "U1") (pin "P$88") (pinfunction "VSS_PAD_P$88") (pintype "bidirectional"))
      (node (ref "U1") (pin "P$89") (pinfunction "VSS_PAD_P$89") (pintype "bidirectional"))
      (node (ref "U1") (pin "P$90") (pinfunction "VSS_PAD_P$90") (pintype "bidirectional"))
      (node (ref "U1") (pin "P$A23") (pinfunction "XC2_P$A23") (pintype "output"))
      (node (ref "U1") (pin "P$B7") (pinfunction "VSS_P$B7") (pintype "power_in"))
      (node (ref "U1") (pin "P$F23") (pinfunction "VSS_PA_P$F23") (pintype "bidirectional"))
      (node (ref "U3") (pin "1") (pinfunction "CTG_1") (pintype "power_in"))
      (node (ref "U3") (pin "4") (pinfunction "GND_4") (pintype "power_in"))
      (node (ref "U3") (pin "6") (pinfunction "QSTRT_6") (pintype "input"))
      (node (ref "U3") (pin "9") (pinfunction "EP_9") (pintype "power_in"))
      (node (ref "X1") (pin "2") (pinfunction "2_2") (pintype "passive"))
      (node (ref "X1") (pin "3") (pinfunction "3_3") (pintype "passive"))
      (node (ref "X1") (pin "4") (pinfunction "4_4") (pintype "passive"))
    )
    (net (code "22") (name "HAPTIC_EN{slash}1.4C") (class "Default")
      (node (ref "IC2") (pin "A1") (pinfunction "EN_A1") (pintype "bidirectional"))
    )
    (net (code "23") (name "HAPTIC_EN{slash}2.6A") (class "Default")
      (node (ref "U1") (pin "P$U1") (pinfunction "P0.12_P$U1") (pintype "bidirectional"))
    )
    (net (code "24") (name "IMU_INT1") (class "Default")
      (node (ref "IC3") (pin "5") (pinfunction "INT1_5") (pintype "bidirectional"))
      (node (ref "U1") (pin "P$N1") (pinfunction "P0.08_P$N1") (pintype "bidirectional"))
    )
    (net (code "25") (name "IMU_INT2") (class "Default")
      (node (ref "IC3") (pin "6") (pinfunction "INT2_6") (pintype "bidirectional"))
      (node (ref "U1") (pin "P$P2") (pinfunction "P1.08_P$P2") (pintype "bidirectional"))
    )
    (net (code "26") (name "LX1") (class "Default")
      (node (ref "IC9") (pin "B2") (pinfunction "SW1_1_B2") (pintype "bidirectional"))
      (node (ref "IC9") (pin "B3") (pinfunction "SW1_2_B3") (pintype "bidirectional"))
      (node (ref "L7") (pin "1") (pinfunction "1_1") (pintype "bidirectional"))
    )
    (net (code "27") (name "LX2") (class "Default")
      (node (ref "IC9") (pin "D2") (pinfunction "SW2_1_D2") (pintype "bidirectional"))
      (node (ref "IC9") (pin "D3") (pinfunction "SW2_2_D3") (pintype "bidirectional"))
      (node (ref "L7") (pin "2") (pinfunction "2_2") (pintype "bidirectional"))
    )
    (net (code "28") (name "MOSI{slash}1.5D") (class "Default")
      (node (ref "J2") (pin "14") (pinfunction "14_14") (pintype "bidirectional"))
    )
    (net (code "29") (name "MOSI{slash}2.2D") (class "Default")
      (node (ref "U1") (pin "P$B13") (pinfunction "P0.03/AIN1_P$B13") (pintype "bidirectional"))
    )
    (net (code "30") (name "Net-(ANT1-FEED)") (class "Default")
      (node (ref "ANT1") (pin "1") (pinfunction "FEED_1") (pintype "input"))
      (node (ref "C22") (pin "2") (pinfunction "2_2") (pintype "passive"))
      (node (ref "C4") (pin "2") (pinfunction "2_2") (pintype "passive"))
      (node (ref "L1") (pin "2") (pinfunction "2_2") (pintype "passive"))
    )
    (net (code "31") (name "Net-(C12-Pad2)") (class "Default")
      (node (ref "C12") (pin "2") (pinfunction "2_2") (pintype "passive"))
      (node (ref "U1") (pin "P$A22") (pinfunction "VDD_P$A22") (pintype "power_in"))
    )
    (net (code "32") (name "Net-(D2-K)") (class "Default")
      (node (ref "D2") (pin "1") (pinfunction "K_1") (pintype "bidirectional"))
      (node (ref "D4") (pin "2") (pinfunction "A_2") (pintype "bidirectional"))
      (node (ref "U$1") (pin "1") (pinfunction "1_1") (pintype "passive"))
    )
    (net (code "33") (name "Net-(D5-A)") (class "Default")
      (node (ref "D5") (pin "2") (pinfunction "A_2") (pintype "bidirectional"))
      (node (ref "L5") (pin "1") (pinfunction "1_1") (pintype "passive"))
      (node (ref "Q3") (pin "3") (pinfunction "D_3") (pintype "bidirectional"))
      (node (ref "U$1") (pin "2") (pinfunction "2_2") (pintype "passive"))
    )
    (net (code "34") (name "Net-(IC1-TS{slash}MR)") (class "Default")
      (node (ref "IC1") (pin "D1") (pinfunction "TS/MR_D1") (pintype "bidirectional"))
      (node (ref "R9") (pin "2") (pinfunction "2_2") (pintype "passive"))
    )
    (net (code "35") (name "Net-(IC2-REG)") (class "Default")
      (node (ref "IC2") (pin "A2") (pinfunction "REG_A2") (pintype "bidirectional"))
      (node (ref "U$12") (pin "1") (pinfunction "1_1") (pintype "passive"))
    )
    (net (code "36") (name "Net-(IC3-SDO)") (class "Default")
      (node (ref "IC3") (pin "1") (pinfunction "SDO_1") (pintype "bidirectional"))
      (node (ref "R3") (pin "1") (pinfunction "1_1") (pintype "passive"))
    )
    (net (code "37") (name "Net-(IC9-SCL)") (class "Default")
      (node (ref "IC9") (pin "D1") (pinfunction "SCL_D1") (pintype "bidirectional"))
      (node (ref "R4") (pin "1") (pinfunction "1_1") (pintype "passive"))
    )
    (net (code "38") (name "Net-(IC9-SDA)") (class "Default")
      (node (ref "IC9") (pin "E1") (pinfunction "SDA_E1") (pintype "bidirectional"))
      (node (ref "R2") (pin "1") (pinfunction "1_1") (pintype "passive"))
    )
    (net (code "39") (name "Net-(J2-Pad4)") (class "Default")
      (node (ref "J2") (pin "4") (pinfunction "4_4") (pintype "bidirectional"))
      (node (ref "U$3") (pin "2") (pinfunction "2_2") (pintype "passive"))
    )
    (net (code "40") (name "Net-(J2-Pad5)") (class "Default")
      (node (ref "J2") (pin "5") (pinfunction "5_5") (pintype "bidirectional"))
      (node (ref "U$2") (pin "2") (pinfunction "2_2") (pintype "passive"))
    )
    (net (code "41") (name "Net-(J2-Pad18)") (class "Default")
      (node (ref "J2") (pin "18") (pinfunction "18_18") (pintype "bidirectional"))
      (node (ref "U$9") (pin "2") (pinfunction "2_2") (pintype "passive"))
    )
    (net (code "42") (name "Net-(J2-Pad19)") (class "Default")
      (node (ref "J2") (pin "19") (pinfunction "19_19") (pintype "bidirectional"))
      (node (ref "U$7") (pin "2") (pinfunction "2_2") (pintype "passive"))
    )
    (net (code "43") (name "Net-(J2-Pad20)") (class "Default")
      (node (ref "J2") (pin "20") (pinfunction "20_20") (pintype "bidirectional"))
      (node (ref "U$11") (pin "2") (pinfunction "2_2") (pintype "passive"))
    )
    (net (code "44") (name "Net-(J2-Pad22)") (class "Default")
      (node (ref "J2") (pin "22") (pinfunction "22_22") (pintype "bidirectional"))
      (node (ref "U$10") (pin "2") (pinfunction "2_2") (pintype "passive"))
    )
    (net (code "45") (name "Net-(J2-Pad24)") (class "Default")
      (node (ref "J2") (pin "24") (pinfunction "24_24") (pintype "bidirectional"))
      (node (ref "U$8") (pin "2") (pinfunction "2_2") (pintype "passive"))
    )
    (net (code "46") (name "Net-(J4-CC1)") (class "Default")
      (node (ref "J4") (pin "A5") (pinfunction "CC1_A5") (pintype "bidirectional"))
      (node (ref "R11") (pin "2") (pinfunction "2_2") (pintype "passive"))
    )
    (net (code "47") (name "Net-(J4-CC2)") (class "Default")
      (node (ref "J4") (pin "B5") (pinfunction "CC2_B5") (pintype "bidirectional"))
      (node (ref "R12") (pin "1") (pinfunction "1_1") (pintype "passive"))
    )
    (net (code "48") (name "Net-(L2-Pad2)") (class "Default")
      (node (ref "L2") (pin "2") (pinfunction "2_2") (pintype "passive"))
      (node (ref "L3") (pin "1") (pinfunction "1_1") (pintype "passive"))
    )
    (net (code "49") (name "Net-(Q3-S)") (class "Default")
      (node (ref "Q3") (pin "2") (pinfunction "S_2") (pintype "bidirectional"))
      (node (ref "R1_EP_DR") (pin "2") (pinfunction "2_2") (pintype "passive"))
    )
    (net (code "50") (name "Net-(R1_EP_DR-Pad1)") (class "Default")
      (node (ref "R1_EP_DR") (pin "1") (pinfunction "1_1") (pintype "passive"))
      (node (ref "R_TYPE_SEL") (pin "2") (pinfunction "2_2") (pintype "passive"))
      (node (ref "SJ1") (pin "2") (pinfunction "2_2") (pintype "passive"))
    )
    (net (code "51") (name "Net-(U1-ANT)") (class "Default")
      (node (ref "C3") (pin "2") (pinfunction "2_2") (pintype "passive"))
      (node (ref "L1") (pin "1") (pinfunction "1_1") (pintype "passive"))
      (node (ref "U1") (pin "P$H23") (pinfunction "ANT_P$H23") (pintype "bidirectional"))
    )
    (net (code "52") (name "Net-(U1-DCC)") (class "Default")
      (node (ref "L2") (pin "1") (pinfunction "1_1") (pintype "passive"))
      (node (ref "U1") (pin "P$B3") (pinfunction "DCC_P$B3") (pintype "output"))
    )
    (net (code "53") (name "Net-(U1-DEC1)") (class "Default")
      (node (ref "C5") (pin "2") (pinfunction "2_2") (pintype "passive"))
      (node (ref "U1") (pin "P$C1") (pinfunction "DEC1_P$C1") (pintype "power_in"))
    )
    (net (code "54") (name "Net-(U1-DEC2)") (class "Default")
      (node (ref "C13") (pin "2") (pinfunction "2_2") (pintype "passive"))
      (node (ref "U1") (pin "P$A18") (pinfunction "DEC2_P$A18") (pintype "bidirectional"))
    )
    (net (code "55") (name "Net-(U1-DEC3)") (class "Default")
      (node (ref "C11") (pin "2") (pinfunction "2_2") (pintype "passive"))
      (node (ref "U1") (pin "P$D23") (pinfunction "DEC3_P$D23") (pintype "bidirectional"))
    )
    (net (code "56") (name "Net-(U1-DEC3V3)") (class "Default")
      (node (ref "C20") (pin "2") (pinfunction "2_2") (pintype "passive"))
      (node (ref "U1") (pin "P$AC5") (pinfunction "DEC3V3_P$AC5") (pintype "bidirectional"))
    )
    (net (code "57") (name "Net-(U1-DEC4)") (class "Default")
      (node (ref "C10") (pin "2") (pinfunction "2_2") (pintype "passive"))
      (node (ref "C15") (pin "2") (pinfunction "2_2") (pintype "passive"))
      (node (ref "C16") (pin "2") (pinfunction "2_2") (pintype "passive"))
      (node (ref "L3") (pin "2") (pinfunction "2_2") (pintype "passive"))
      (node (ref "U1") (pin "P$B5") (pinfunction "DEC4_P$B5") (pintype "power_in"))
      (node (ref "U1") (pin "P$E24") (pinfunction "DEC6_P$E24") (pintype "bidirectional"))
    )
    (net (code "58") (name "Net-(U1-DEC5)") (class "Default")
      (node (ref "C9") (pin "2") (pinfunction "2_2") (pintype "passive"))
      (node (ref "U1") (pin "P$N24") (pinfunction "DEC5_P$N24") (pintype "bidirectional"))
    )
    (net (code "59") (name "Net-(U1-P0.00{slash}XL1)") (class "Default")
      (node (ref "C17") (pin "2") (pinfunction "2_2") (pintype "passive"))
      (node (ref "U1") (pin "P$D2") (pinfunction "P0.00/XL1_P$D2") (pintype "bidirectional"))
      (node (ref "X2") (pin "1") (pinfunction "1_1") (pintype "passive"))
    )
    (net (code "60") (name "Net-(U1-P0.01{slash}XL2)") (class "Default")
      (node (ref "C18") (pin "2") (pinfunction "2_2") (pintype "passive"))
      (node (ref "U1") (pin "P$F2") (pinfunction "P0.01/XL2_P$F2") (pintype "bidirectional"))
      (node (ref "X2") (pin "2") (pinfunction "2_2") (pintype "passive"))
    )
    (net (code "61") (name "Net-(U1-XC1)") (class "Default")
      (node (ref "C1") (pin "2") (pinfunction "2_2") (pintype "passive"))
      (node (ref "U1") (pin "P$B24") (pinfunction "XC1_P$B24") (pintype "input"))
      (node (ref "X1") (pin "1") (pinfunction "1_1") (pintype "passive"))
    )
    (net (code "62") (name "OUT+") (class "Default")
      (node (ref "IC2") (pin "A3") (pinfunction "OUT+_A3") (pintype "bidirectional"))
      (node (ref "TP_OP") (pin "TP") (pinfunction "TP_TP") (pintype "input"))
    )
    (net (code "63") (name "OUT-") (class "Default")
      (node (ref "IC2") (pin "C3") (pinfunction "OUT-_C3") (pintype "bidirectional"))
      (node (ref "TP_ON") (pin "TP") (pinfunction "TP_TP") (pintype "input"))
    )
    (net (code "64") (name "P0.04") (class "Default")
      (node (ref "U1") (pin "P$J1") (pinfunction "P0.04/AIN2_P$J1") (pintype "bidirectional"))
    )
    (net (code "65") (name "P0.09") (class "Default")
      (node (ref "U1") (pin "P$L24") (pinfunction "P0.09/NFC1_P$L24") (pintype "bidirectional"))
    )
    (net (code "66") (name "P0.13{slash}1.5D") (class "Default")
      (node (ref "R10") (pin "1") (pinfunction "1_1") (pintype "passive"))
      (node (ref "SW2") (pin "2") (pinfunction "2_2") (pintype "passive"))
      (node (ref "U$14") (pin "1") (pinfunction "1_1") (pintype "passive"))
    )
    (net (code "67") (name "P0.14{slash}1.5D") (class "Default")
      (node (ref "R8") (pin "1") (pinfunction "1_1") (pintype "passive"))
      (node (ref "SW1") (pin "2") (pinfunction "2_2") (pintype "passive"))
      (node (ref "U$15") (pin "1") (pinfunction "1_1") (pintype "passive"))
    )
    (net (code "68") (name "P0.14{slash}2.7C") (class "Default")
      (node (ref "U1") (pin "P$AC9") (pinfunction "P0.14_P$AC9") (pintype "bidirectional"))
    )
    (net (code "69") (name "P0.19") (class "Default")
      (node (ref "U1") (pin "P$AC15") (pinfunction "P0.19_P$AC15") (pintype "bidirectional"))
    )
    (net (code "70") (name "P0.20") (class "Default")
      (node (ref "U1") (pin "P$AD16") (pinfunction "P0.20_P$AD16") (pintype "bidirectional"))
    )
    (net (code "71") (name "P0.21") (class "Default")
      (node (ref "U1") (pin "P$AC17") (pinfunction "P0.21_P$AC17") (pintype "bidirectional"))
    )
    (net (code "72") (name "P0.22") (class "Default")
      (node (ref "U1") (pin "P$AD18") (pinfunction "P0.22_P$AD18") (pintype "bidirectional"))
    )
    (net (code "73") (name "P0.23") (class "Default")
      (node (ref "U1") (pin "P$AC19") (pinfunction "P0.23_P$AC19") (pintype "bidirectional"))
    )
    (net (code "74") (name "P0.24") (class "Default")
      (node (ref "U1") (pin "P$AD20") (pinfunction "P0.24_P$AD20") (pintype "bidirectional"))
    )
    (net (code "75") (name "P0.25") (class "Default")
      (node (ref "U1") (pin "P$AC21") (pinfunction "P0.25_P$AC21") (pintype "bidirectional"))
    )
    (net (code "76") (name "P0.26") (class "Default")
      (node (ref "U1") (pin "P$G1") (pinfunction "P0.26_P$G1") (pintype "bidirectional"))
    )
    (net (code "77") (name "P0.27") (class "Default")
      (node (ref "U1") (pin "P$H2") (pinfunction "P0.27_P$H2") (pintype "bidirectional"))
    )
    (net (code "78") (name "P0.28") (class "Default")
      (node (ref "U1") (pin "P$B11") (pinfunction "P0.28/AIN4_P$B11") (pintype "bidirectional"))
    )
    (net (code "79") (name "P0.29") (class "Default")
      (node (ref "U1") (pin "P$A10") (pinfunction "P0.29/AIN5_P$A10") (pintype "bidirectional"))
    )
    (net (code "80") (name "P0.30") (class "Default")
      (node (ref "U1") (pin "P$B9") (pinfunction "P0.30/AIN6_P$B9") (pintype "bidirectional"))
    )
    (net (code "81") (name "P0.31") (class "Default")
      (node (ref "U1") (pin "P$A8") (pinfunction "P0.31/AIN7_P$A8") (pintype "bidirectional"))
    )
    (net (code "82") (name "P1.01{slash}1.6C") (class "Default")
      (node (ref "Q1") (pin "1") (pinfunction "G_1") (pintype "bidirectional"))
      (node (ref "R6") (pin "1") (pinfunction "1_1") (pintype "passive"))
    )
    (net (code "83") (name "P1.01{slash}2.4B") (class "Default")
      (node (ref "U1") (pin "P$Y23") (pinfunction "P1.01_P$Y23") (pintype "bidirectional"))
    )
    (net (code "84") (name "P1.02{slash}1.6C") (class "Default")
      (node (ref "R7") (pin "1") (pinfunction "1_1") (pintype "passive"))
      (node (ref "SW3") (pin "2") (pinfunction "2_2") (pintype "passive"))
      (node (ref "U$16") (pin "1") (pinfunction "1_1") (pintype "passive"))
    )
    (net (code "85") (name "P1.02{slash}2.8C") (class "Default")
      (node (ref "U1") (pin "P$W24") (pinfunction "P1.02_P$W24") (pintype "bidirectional"))
    )
    (net (code "86") (name "P1.03") (class "Default")
      (node (ref "U1") (pin "P$V23") (pinfunction "P1.03_P$V23") (pintype "bidirectional"))
    )
    (net (code "87") (name "P1.04") (class "Default")
      (node (ref "U1") (pin "P$U24") (pinfunction "P1.04_P$U24") (pintype "bidirectional"))
    )
    (net (code "88") (name "P1.05") (class "Default")
      (node (ref "U1") (pin "P$T23") (pinfunction "P1.05_P$T23") (pintype "bidirectional"))
    )
    (net (code "89") (name "P1.06") (class "Default")
      (node (ref "U1") (pin "P$R24") (pinfunction "P1.06_P$R24") (pintype "bidirectional"))
    )
    (net (code "90") (name "P1.07") (class "Default")
      (node (ref "U1") (pin "P$P23") (pinfunction "P1.07_P$P23") (pintype "bidirectional"))
    )
    (net (code "91") (name "P1.09") (class "Default")
      (node (ref "U1") (pin "P$R1") (pinfunction "P1.09_P$R1") (pintype "bidirectional"))
    )
    (net (code "92") (name "P1.10") (class "Default")
      (node (ref "U1") (pin "P$A20") (pinfunction "P1.10_P$A20") (pintype "bidirectional"))
    )
    (net (code "93") (name "P1.11") (class "Default")
      (node (ref "U1") (pin "P$B19") (pinfunction "P1.11_P$B19") (pintype "bidirectional"))
    )
    (net (code "94") (name "P1.12") (class "Default")
      (node (ref "U1") (pin "P$B17") (pinfunction "P1.12_P$B17") (pintype "bidirectional"))
    )
    (net (code "95") (name "P1.13") (class "Default")
      (node (ref "U1") (pin "P$A16") (pinfunction "P1.13_P$A16") (pintype "bidirectional"))
    )
    (net (code "96") (name "P1.14") (class "Default")
      (node (ref "U1") (pin "P$B15") (pinfunction "P1.14_P$B15") (pintype "bidirectional"))
    )
    (net (code "97") (name "P1.15") (class "Default")
      (node (ref "U1") (pin "P$A14") (pinfunction "P1.15_P$A14") (pintype "bidirectional"))
    )
    (net (code "98") (name "PMIC_INT") (class "Default")
      (node (ref "IC1") (pin "A1") (pinfunction "~{INT}_A1") (pintype "bidirectional"))
      (node (ref "U1") (pin "P$T2") (pinfunction "P0.11_P$T2") (pintype "bidirectional"))
    )
    (net (code "99") (name "PO.13{slash}2.6C") (class "Default")
      (node (ref "U1") (pin "P$AD8") (pinfunction "P0.13_P$AD8") (pintype "bidirectional"))
    )
    (net (code "100") (name "PREVGH") (class "Default")
      (node (ref "D5") (pin "1") (pinfunction "K_1") (pintype "bidirectional"))
      (node (ref "J2") (pin "21") (pinfunction "21_21") (pintype "bidirectional"))
      (node (ref "U$5") (pin "2") (pinfunction "2_2") (pintype "passive"))
    )
    (net (code "101") (name "PREVGL") (class "Default")
      (node (ref "D2") (pin "2") (pinfunction "A_2") (pintype "bidirectional"))
      (node (ref "J2") (pin "23") (pinfunction "23_23") (pintype "bidirectional"))
      (node (ref "U$6") (pin "2") (pinfunction "2_2") (pintype "passive"))
    )
    (net (code "102") (name "RESE") (class "Default")
      (node (ref "J2") (pin "3") (pinfunction "3_3") (pintype "bidirectional"))
    )
    (net (code "103") (name "RESET") (class "Default")
      (node (ref "J1") (pin "6") (pinfunction "6_6") (pintype "bidirectional"))
      (node (ref "TP_RESET") (pin "TP") (pinfunction "TP_TP") (pintype "input"))
      (node (ref "U1") (pin "P$AC13") (pinfunction "P0.18/RESET_P$AC13") (pintype "bidirectional"))
    )
    (net (code "104") (name "SCK{slash}1.5D") (class "Default")
      (node (ref "J2") (pin "13") (pinfunction "13_13") (pintype "bidirectional"))
    )
    (net (code "105") (name "SCK{slash}2.2D") (class "Default")
      (node (ref "U1") (pin "P$A12") (pinfunction "P0.02/AIN0_P$A12") (pintype "bidirectional"))
    )
    (net (code "106") (name "SCL{slash}1.4C") (class "Default")
      (node (ref "IC2") (pin "C1") (pinfunction "SCL_C1") (pintype "bidirectional"))
      (node (ref "U3") (pin "7") (pinfunction "SCL_7") (pintype "input"))
    )
    (net (code "107") (name "SCL{slash}2.4C") (class "Default")
      (node (ref "IC1") (pin "B1") (pinfunction "SCL_B1") (pintype "bidirectional"))
      (node (ref "IC3") (pin "12") (pinfunction "SCX_12") (pintype "bidirectional"))
      (node (ref "R4") (pin "2") (pinfunction "2_2") (pintype "passive"))
      (node (ref "R5") (pin "2") (pinfunction "2_2") (pintype "passive"))
      (node (ref "TP_SCL") (pin "TP") (pinfunction "TP_TP") (pintype "input"))
      (node (ref "U1") (pin "P$M2") (pinfunction "P0.07_P$M2") (pintype "bidirectional"))
    )
    (net (code "108") (name "SDA{slash}1.4C") (class "Default")
      (node (ref "IC2") (pin "B2") (pinfunction "SDA_B2") (pintype "bidirectional"))
      (node (ref "U3") (pin "8") (pinfunction "SDA_8") (pintype "bidirectional"))
    )
    (net (code "109") (name "SDA{slash}2.4C") (class "Default")
      (node (ref "IC1") (pin "C1") (pinfunction "SDA_C1") (pintype "bidirectional"))
      (node (ref "IC3") (pin "2") (pinfunction "SDX_2") (pintype "bidirectional"))
      (node (ref "R1") (pin "2") (pinfunction "2_2") (pintype "passive"))
      (node (ref "R2") (pin "2") (pinfunction "2_2") (pintype "passive"))
      (node (ref "TP_SDA") (pin "TP") (pinfunction "TP_TP") (pintype "input"))
      (node (ref "U1") (pin "P$L1") (pinfunction "P0.06_P$L1") (pintype "bidirectional"))
    )
    (net (code "110") (name "SWDCLK") (class "Default")
      (node (ref "J1") (pin "4") (pinfunction "4_4") (pintype "bidirectional"))
      (node (ref "TP_SWDCLK") (pin "TP") (pinfunction "TP_TP") (pintype "input"))
      (node (ref "U1") (pin "P$AA24") (pinfunction "SWDCLK_P$AA24") (pintype "input"))
    )
    (net (code "111") (name "SWDIO") (class "Default")
      (node (ref "J1") (pin "2") (pinfunction "2_2") (pintype "bidirectional"))
      (node (ref "TP_SWDIO") (pin "TP") (pinfunction "TP_TP") (pintype "input"))
      (node (ref "U1") (pin "P$AC24") (pinfunction "SWDIO_P$AC24") (pintype "bidirectional"))
    )
    (net (code "112") (name "SWO") (class "Default")
      (node (ref "TP_SWO") (pin "TP") (pinfunction "TP_TP") (pintype "input"))
      (node (ref "U1") (pin "P$AD22") (pinfunction "P1.00_P$AD22") (pintype "bidirectional"))
    )
    (net (code "113") (name "VBAT{slash}1.2A") (class "Default")
      (node (ref "TP_VBAT") (pin "TP") (pinfunction "TP_TP") (pintype "input"))
      (node (ref "U$19") (pin "1") (pinfunction "1_1") (pintype "passive"))
      (node (ref "U3") (pin "2") (pinfunction "CELL_2") (pintype "power_in"))
      (node (ref "U3") (pin "3") (pinfunction "VDD_3") (pintype "power_in"))
    )
    (net (code "114") (name "VBAT{slash}2.5C") (class "Default")
      (node (ref "C37") (pin "1") (pinfunction "1_1") (pintype "passive"))
      (node (ref "IC1") (pin "C2") (pinfunction "BAT_C2") (pintype "bidirectional"))
    )
    (net (code "115") (name "VBUS{slash}1.5D") (class "Default")
      (node (ref "D3") (pin "5") (pinfunction "VBUS_5") (pintype "bidirectional"))
      (node (ref "J4") (pin "A4_B9") (pinfunction "VBUS_A4_B9") (pintype "power_in"))
      (node (ref "J4") (pin "A9_B4") (pinfunction "VBUS_A9_B4") (pintype "power_in"))
      (node (ref "U$17") (pin "1") (pinfunction "1_1") (pintype "passive"))
      (node (ref "U$18") (pin "1") (pinfunction "1_1") (pintype "passive"))
    )
    (net (code "116") (name "VBUS{slash}2.6D") (class "Default")
      (node (ref "C21") (pin "2") (pinfunction "2_2") (pintype "passive"))
      (node (ref "C38") (pin "2") (pinfunction "2_2") (pintype "passive"))
      (node (ref "IC1") (pin "A2") (pinfunction "IN_A2") (pintype "bidirectional"))
      (node (ref "U1") (pin "P$AD2") (pinfunction "VBUS_P$AD2") (pintype "power_in"))
    )
    (net (code "117") (name "VREG") (class "Default")
      (node (ref "C23") (pin "2") (pinfunction "2_2") (pintype "passive"))
      (node (ref "C24") (pin "2") (pinfunction "2_2") (pintype "passive"))
      (node (ref "C39") (pin "1") (pinfunction "1_1") (pintype "passive"))
      (node (ref "IC1") (pin "B2") (pinfunction "SYS_B2") (pintype "bidirectional"))
      (node (ref "IC9") (pin "A1") (pinfunction "EN_A1") (pintype "bidirectional"))
      (node (ref "IC9") (pin "A2") (pinfunction "VIN_1_A2") (pintype "bidirectional"))
      (node (ref "IC9") (pin "A3") (pinfunction "VIN_2_A3") (pintype "bidirectional"))
      (node (ref "TP_VREG") (pin "TP") (pinfunction "TP_TP") (pintype "input"))
    )
    (net (code "118") (name "unconnected-(ANT1-NC-Pad2)") (class "Default")
      (node (ref "ANT1") (pin "2") (pinfunction "NC_2") (pintype "no_connect"))
    )
    (net (code "119") (name "unconnected-(IC3-ASCL-Pad11)") (class "Default")
      (node (ref "IC3") (pin "11") (pinfunction "ASCL_11") (pintype "bidirectional"))
    )
    (net (code "120") (name "unconnected-(IC3-ASDA-Pad4)") (class "Default")
      (node (ref "IC3") (pin "4") (pinfunction "ASDA_4") (pintype "bidirectional"))
    )
    (net (code "121") (name "unconnected-(J2-Pad1)") (class "Default")
      (node (ref "J2") (pin "1") (pinfunction "1_1") (pintype "bidirectional"))
    )
    (net (code "122") (name "unconnected-(J2-Pad6)") (class "Default")
      (node (ref "J2") (pin "6") (pinfunction "6_6") (pintype "bidirectional"))
    )
    (net (code "123") (name "unconnected-(J2-Pad7)") (class "Default")
      (node (ref "J2") (pin "7") (pinfunction "7_7") (pintype "bidirectional"))
    )
    (net (code "124") (name "unconnected-(J4-SBU1-PadA8)") (class "Default")
      (node (ref "J4") (pin "A8") (pinfunction "SBU1_A8") (pintype "bidirectional"))
    )
    (net (code "125") (name "unconnected-(J4-SBU2-PadB8)") (class "Default")
      (node (ref "J4") (pin "B8") (pinfunction "SBU2_B8") (pintype "bidirectional"))
    )
    (net (code "126") (name "unconnected-(U$13-Pad2)") (class "Default")
      (node (ref "U$13") (pin "2") (pinfunction "2_2") (pintype "passive"))
    )
    (net (code "127") (name "unconnected-(U1-DCCH-PadP$AB2)") (class "Default")
      (node (ref "U1") (pin "P$AB2") (pinfunction "DCCH_P$AB2") (pintype "bidirectional"))
    )
  )
)
